# untitled.net
KiCad netlist of a schematic drawn in EAGLE
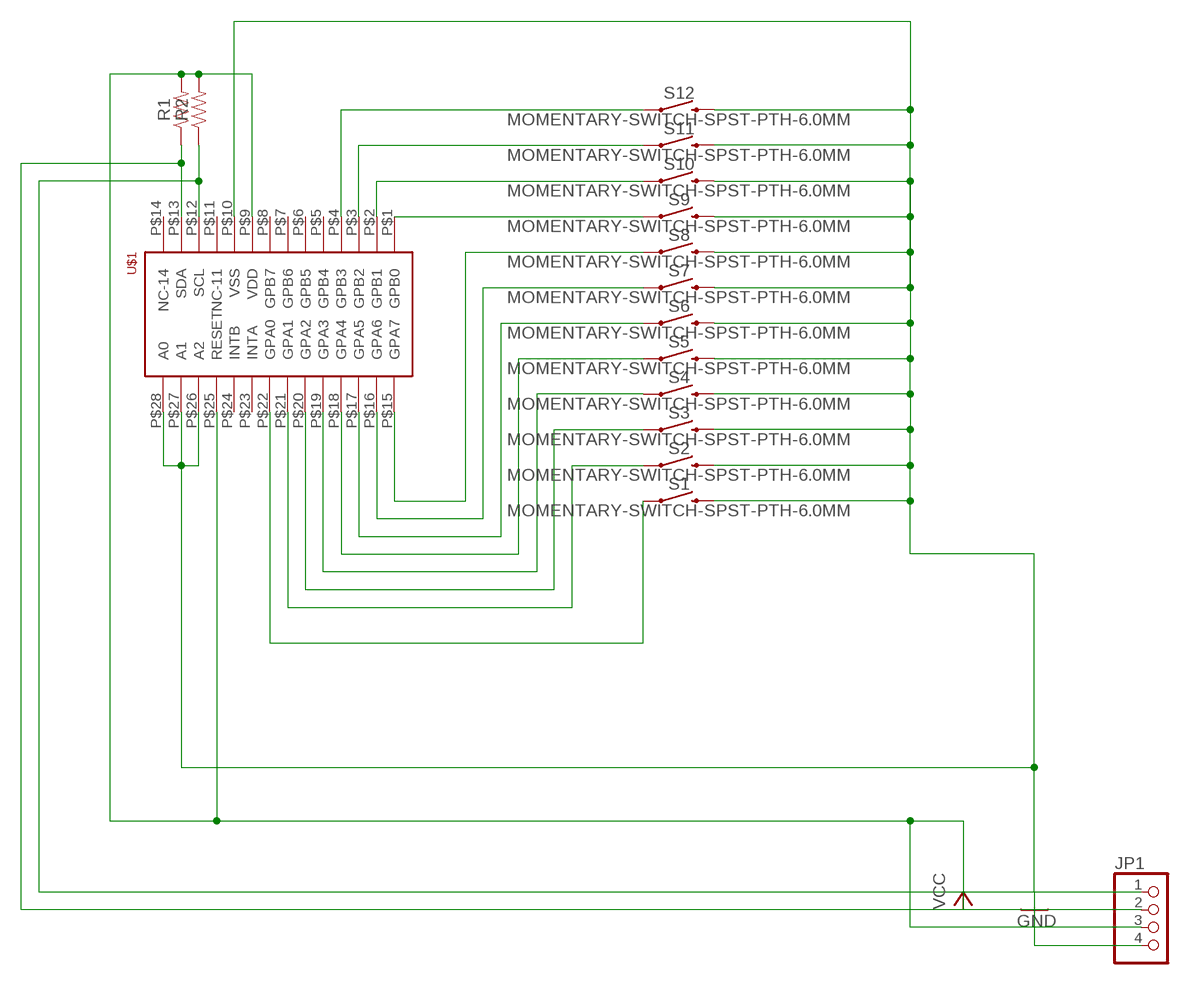
[diagram p0: schematic, sheet 1]

(export (version "E")
  (design (tool "Eeschema 10.0.6"))
  (components
    (comp (ref "JP1")
      (value "PINHD-1X4")
      (footprint "eagle-import:1X04")
      (fields (field (name "SPICEPREFIX") "B"))
      (libsource (lib "eagle-import") (part "PINHD-1X4"))
    )
    (comp (ref "R1")
      (value "RESISTORAXIAL-0.3")
      (footprint "eagle-import:AXIAL-0.3")
      (libsource (lib "eagle-import") (part "RESISTORAXIAL-0.3"))
    )
    (comp (ref "R2")
      (value "RESISTORAXIAL-0.3")
      (footprint "eagle-import:AXIAL-0.3")
      (libsource (lib "eagle-import") (part "RESISTORAXIAL-0.3"))
    )
    (comp (ref "S1")
      (value "MOMENTARY-SWITCH-SPST-PTH-6.0MM")
      (footprint "eagle-import:TACTILE_SWITCH_PTH_6.0MM")
      (libsource (lib "eagle-import") (part "MOMENTARY-SWITCH-SPST-PTH-6.0MM"))
    )
    (comp (ref "S2")
      (value "MOMENTARY-SWITCH-SPST-PTH-6.0MM")
      (footprint "eagle-import:TACTILE_SWITCH_PTH_6.0MM")
      (libsource (lib "eagle-import") (part "MOMENTARY-SWITCH-SPST-PTH-6.0MM"))
    )
    (comp (ref "S3")
      (value "MOMENTARY-SWITCH-SPST-PTH-6.0MM")
      (footprint "eagle-import:TACTILE_SWITCH_PTH_6.0MM")
      (libsource (lib "eagle-import") (part "MOMENTARY-SWITCH-SPST-PTH-6.0MM"))
    )
    (comp (ref "S4")
      (value "MOMENTARY-SWITCH-SPST-PTH-6.0MM")
      (footprint "eagle-import:TACTILE_SWITCH_PTH_6.0MM")
      (libsource (lib "eagle-import") (part "MOMENTARY-SWITCH-SPST-PTH-6.0MM"))
    )
    (comp (ref "S5")
      (value "MOMENTARY-SWITCH-SPST-PTH-6.0MM")
      (footprint "eagle-import:TACTILE_SWITCH_PTH_6.0MM")
      (libsource (lib "eagle-import") (part "MOMENTARY-SWITCH-SPST-PTH-6.0MM"))
    )
    (comp (ref "S6")
      (value "MOMENTARY-SWITCH-SPST-PTH-6.0MM")
      (footprint "eagle-import:TACTILE_SWITCH_PTH_6.0MM")
      (libsource (lib "eagle-import") (part "MOMENTARY-SWITCH-SPST-PTH-6.0MM"))
    )
    (comp (ref "S7")
      (value "MOMENTARY-SWITCH-SPST-PTH-6.0MM")
      (footprint "eagle-import:TACTILE_SWITCH_PTH_6.0MM")
      (libsource (lib "eagle-import") (part "MOMENTARY-SWITCH-SPST-PTH-6.0MM"))
    )
    (comp (ref "S8")
      (value "MOMENTARY-SWITCH-SPST-PTH-6.0MM")
      (footprint "eagle-import:TACTILE_SWITCH_PTH_6.0MM")
      (libsource (lib "eagle-import") (part "MOMENTARY-SWITCH-SPST-PTH-6.0MM"))
    )
    (comp (ref "S9")
      (value "MOMENTARY-SWITCH-SPST-PTH-6.0MM")
      (footprint "eagle-import:TACTILE_SWITCH_PTH_6.0MM")
      (libsource (lib "eagle-import") (part "MOMENTARY-SWITCH-SPST-PTH-6.0MM"))
    )
    (comp (ref "S10")
      (value "MOMENTARY-SWITCH-SPST-PTH-6.0MM")
      (footprint "eagle-import:TACTILE_SWITCH_PTH_6.0MM")
      (libsource (lib "eagle-import") (part "MOMENTARY-SWITCH-SPST-PTH-6.0MM"))
    )
    (comp (ref "S11")
      (value "MOMENTARY-SWITCH-SPST-PTH-6.0MM")
      (footprint "eagle-import:TACTILE_SWITCH_PTH_6.0MM")
      (libsource (lib "eagle-import") (part "MOMENTARY-SWITCH-SPST-PTH-6.0MM"))
    )
    (comp (ref "S12")
      (value "MOMENTARY-SWITCH-SPST-PTH-6.0MM")
      (footprint "eagle-import:TACTILE_SWITCH_PTH_6.0MM")
      (libsource (lib "eagle-import") (part "MOMENTARY-SWITCH-SPST-PTH-6.0MM"))
    )
    (comp (ref "U$1")
      (value "MCP23017-E/SP")
      (footprint "eagle-import:DIP28")
      (libsource (lib "eagle-import") (part "MCP23017-E/SP"))
    )
  )
  (nets
    (net (code "1") (name "GND") (class "Default")
      (node (ref "JP1") (pin "4") (pinfunction "4_4") (pintype "passive"))
      (node (ref "S1") (pin "3") (pinfunction "2_3") (pintype "passive"))
      (node (ref "S10") (pin "3") (pinfunction "2_3") (pintype "passive"))
      (node (ref "S11") (pin "3") (pinfunction "2_3") (pintype "passive"))
      (node (ref "S12") (pin "3") (pinfunction "2_3") (pintype "passive"))
      (node (ref "S2") (pin "3") (pinfunction "2_3") (pintype "passive"))
      (node (ref "S3") (pin "3") (pinfunction "2_3") (pintype "passive"))
      (node (ref "S4") (pin "3") (pinfunction "2_3") (pintype "passive"))
      (node (ref "S5") (pin "3") (pinfunction "2_3") (pintype "passive"))
      (node (ref "S6") (pin "3") (pinfunction "2_3") (pintype "passive"))
      (node (ref "S7") (pin "3") (pinfunction "2_3") (pintype "passive"))
      (node (ref "S8") (pin "3") (pinfunction "2_3") (pintype "passive"))
      (node (ref "S9") (pin "3") (pinfunction "2_3") (pintype "passive"))
      (node (ref "U$1") (pin "P$10") (pinfunction "VSS_P$10") (pintype "bidirectional"))
      (node (ref "U$1") (pin "P$26") (pinfunction "A2_P$26") (pintype "bidirectional"))
      (node (ref "U$1") (pin "P$27") (pinfunction "A1_P$27") (pintype "bidirectional"))
      (node (ref "U$1") (pin "P$28") (pinfunction "A0_P$28") (pintype "bidirectional"))
    )
    (net (code "2") (name "Net-(R1-1)") (class "Default")
      (node (ref "JP1") (pin "2") (pinfunction "2_2") (pintype "passive"))
      (node (ref "R1") (pin "P$1") (pinfunction "1_P$1") (pintype "passive"))
      (node (ref "U$1") (pin "P$13") (pinfunction "SDA_P$13") (pintype "bidirectional"))
    )
    (net (code "3") (name "Net-(R2-1)") (class "Default")
      (node (ref "JP1") (pin "1") (pinfunction "1_1") (pintype "passive"))
      (node (ref "R2") (pin "P$1") (pinfunction "1_P$1") (pintype "passive"))
      (node (ref "U$1") (pin "P$12") (pinfunction "SCL_P$12") (pintype "bidirectional"))
    )
    (net (code "4") (name "Net-(U$1-GPA0)") (class "Default")
      (node (ref "S1") (pin "1") (pinfunction "1_1") (pintype "passive"))
      (node (ref "U$1") (pin "P$22") (pinfunction "GPA0_P$22") (pintype "bidirectional"))
    )
    (net (code "5") (name "Net-(U$1-GPA1)") (class "Default")
      (node (ref "S2") (pin "1") (pinfunction "1_1") (pintype "passive"))
      (node (ref "U$1") (pin "P$21") (pinfunction "GPA1_P$21") (pintype "bidirectional"))
    )
    (net (code "6") (name "Net-(U$1-GPA2)") (class "Default")
      (node (ref "S3") (pin "1") (pinfunction "1_1") (pintype "passive"))
      (node (ref "U$1") (pin "P$20") (pinfunction "GPA2_P$20") (pintype "bidirectional"))
    )
    (net (code "7") (name "Net-(U$1-GPA3)") (class "Default")
      (node (ref "S4") (pin "1") (pinfunction "1_1") (pintype "passive"))
      (node (ref "U$1") (pin "P$19") (pinfunction "GPA3_P$19") (pintype "bidirectional"))
    )
    (net (code "8") (name "Net-(U$1-GPA4)") (class "Default")
      (node (ref "S5") (pin "1") (pinfunction "1_1") (pintype "passive"))
      (node (ref "U$1") (pin "P$18") (pinfunction "GPA4_P$18") (pintype "bidirectional"))
    )
    (net (code "9") (name "Net-(U$1-GPA5)") (class "Default")
      (node (ref "S6") (pin "1") (pinfunction "1_1") (pintype "passive"))
      (node (ref "U$1") (pin "P$17") (pinfunction "GPA5_P$17") (pintype "bidirectional"))
    )
    (net (code "10") (name "Net-(U$1-GPA6)") (class "Default")
      (node (ref "S7") (pin "1") (pinfunction "1_1") (pintype "passive"))
      (node (ref "U$1") (pin "P$16") (pinfunction "GPA6_P$16") (pintype "bidirectional"))
    )
    (net (code "11") (name "Net-(U$1-GPA7)") (class "Default")
      (node (ref "S8") (pin "1") (pinfunction "1_1") (pintype "passive"))
      (node (ref "U$1") (pin "P$15") (pinfunction "GPA7_P$15") (pintype "bidirectional"))
    )
    (net (code "12") (name "Net-(U$1-GPB0)") (class "Default")
      (node (ref "S9") (pin "1") (pinfunction "1_1") (pintype "passive"))
      (node (ref "U$1") (pin "P$1") (pinfunction "GPB0_P$1") (pintype "bidirectional"))
    )
    (net (code "13") (name "Net-(U$1-GPB1)") (class "Default")
      (node (ref "S10") (pin "1") (pinfunction "1_1") (pintype "passive"))
      (node (ref "U$1") (pin "P$2") (pinfunction "GPB1_P$2") (pintype "bidirectional"))
    )
    (net (code "14") (name "Net-(U$1-GPB2)") (class "Default")
      (node (ref "S11") (pin "1") (pinfunction "1_1") (pintype "passive"))
      (node (ref "U$1") (pin "P$3") (pinfunction "GPB2_P$3") (pintype "bidirectional"))
    )
    (net (code "15") (name "Net-(U$1-GPB3)") (class "Default")
      (node (ref "S12") (pin "1") (pinfunction "1_1") (pintype "passive"))
      (node (ref "U$1") (pin "P$4") (pinfunction "GPB3_P$4") (pintype "bidirectional"))
    )
    (net (code "16") (name "VCC") (class "Default")
      (node (ref "JP1") (pin "3") (pinfunction "3_3") (pintype "passive"))
      (node (ref "R1") (pin "P$2") (pinfunction "2_P$2") (pintype "passive"))
      (node (ref "R2") (pin "P$2") (pinfunction "2_P$2") (pintype "passive"))
      (node (ref "U$1") (pin "P$25") (pinfunction "RESET_P$25") (pintype "bidirectional"))
      (node (ref "U$1") (pin "P$9") (pinfunction "VDD_P$9") (pintype "bidirectional"))
    )
    (net (code "17") (name "unconnected-(U$1-GPB4-PadP$5)") (class "Default")
      (node (ref "U$1") (pin "P$5") (pinfunction "GPB4_P$5") (pintype "bidirectional"))
    )
    (net (code "18") (name "unconnected-(U$1-GPB5-PadP$6)") (class "Default")
      (node (ref "U$1") (pin "P$6") (pinfunction "GPB5_P$6") (pintype "bidirectional"))
    )
    (net (code "19") (name "unconnected-(U$1-GPB6-PadP$7)") (class "Default")
      (node (ref "U$1") (pin "P$7") (pinfunction "GPB6_P$7") (pintype "bidirectional"))
    )
    (net (code "20") (name "unconnected-(U$1-GPB7-PadP$8)") (class "Default")
      (node (ref "U$1") (pin "P$8") (pinfunction "GPB7_P$8") (pintype "bidirectional"))
    )
    (net (code "21") (name "unconnected-(U$1-INTA-PadP$23)") (class "Default")
      (node (ref "U$1") (pin "P$23") (pinfunction "INTA_P$23") (pintype "bidirectional"))
    )
    (net (code "22") (name "unconnected-(U$1-INTB-PadP$24)") (class "Default")
      (node (ref "U$1") (pin "P$24") (pinfunction "INTB_P$24") (pintype "bidirectional"))
    )
    (net (code "23") (name "unconnected-(U$1-NC-11-PadP$11)") (class "Default")
      (node (ref "U$1") (pin "P$11") (pinfunction "NC-11_P$11") (pintype "bidirectional"))
    )
    (net (code "24") (name "unconnected-(U$1-NC-14-PadP$14)") (class "Default")
      (node (ref "U$1") (pin "P$14") (pinfunction "NC-14_P$14") (pintype "bidirectional"))
    )
  )
)
